# Bluetooth.net
KiCad netlist of a schematic drawn in Altium Designer
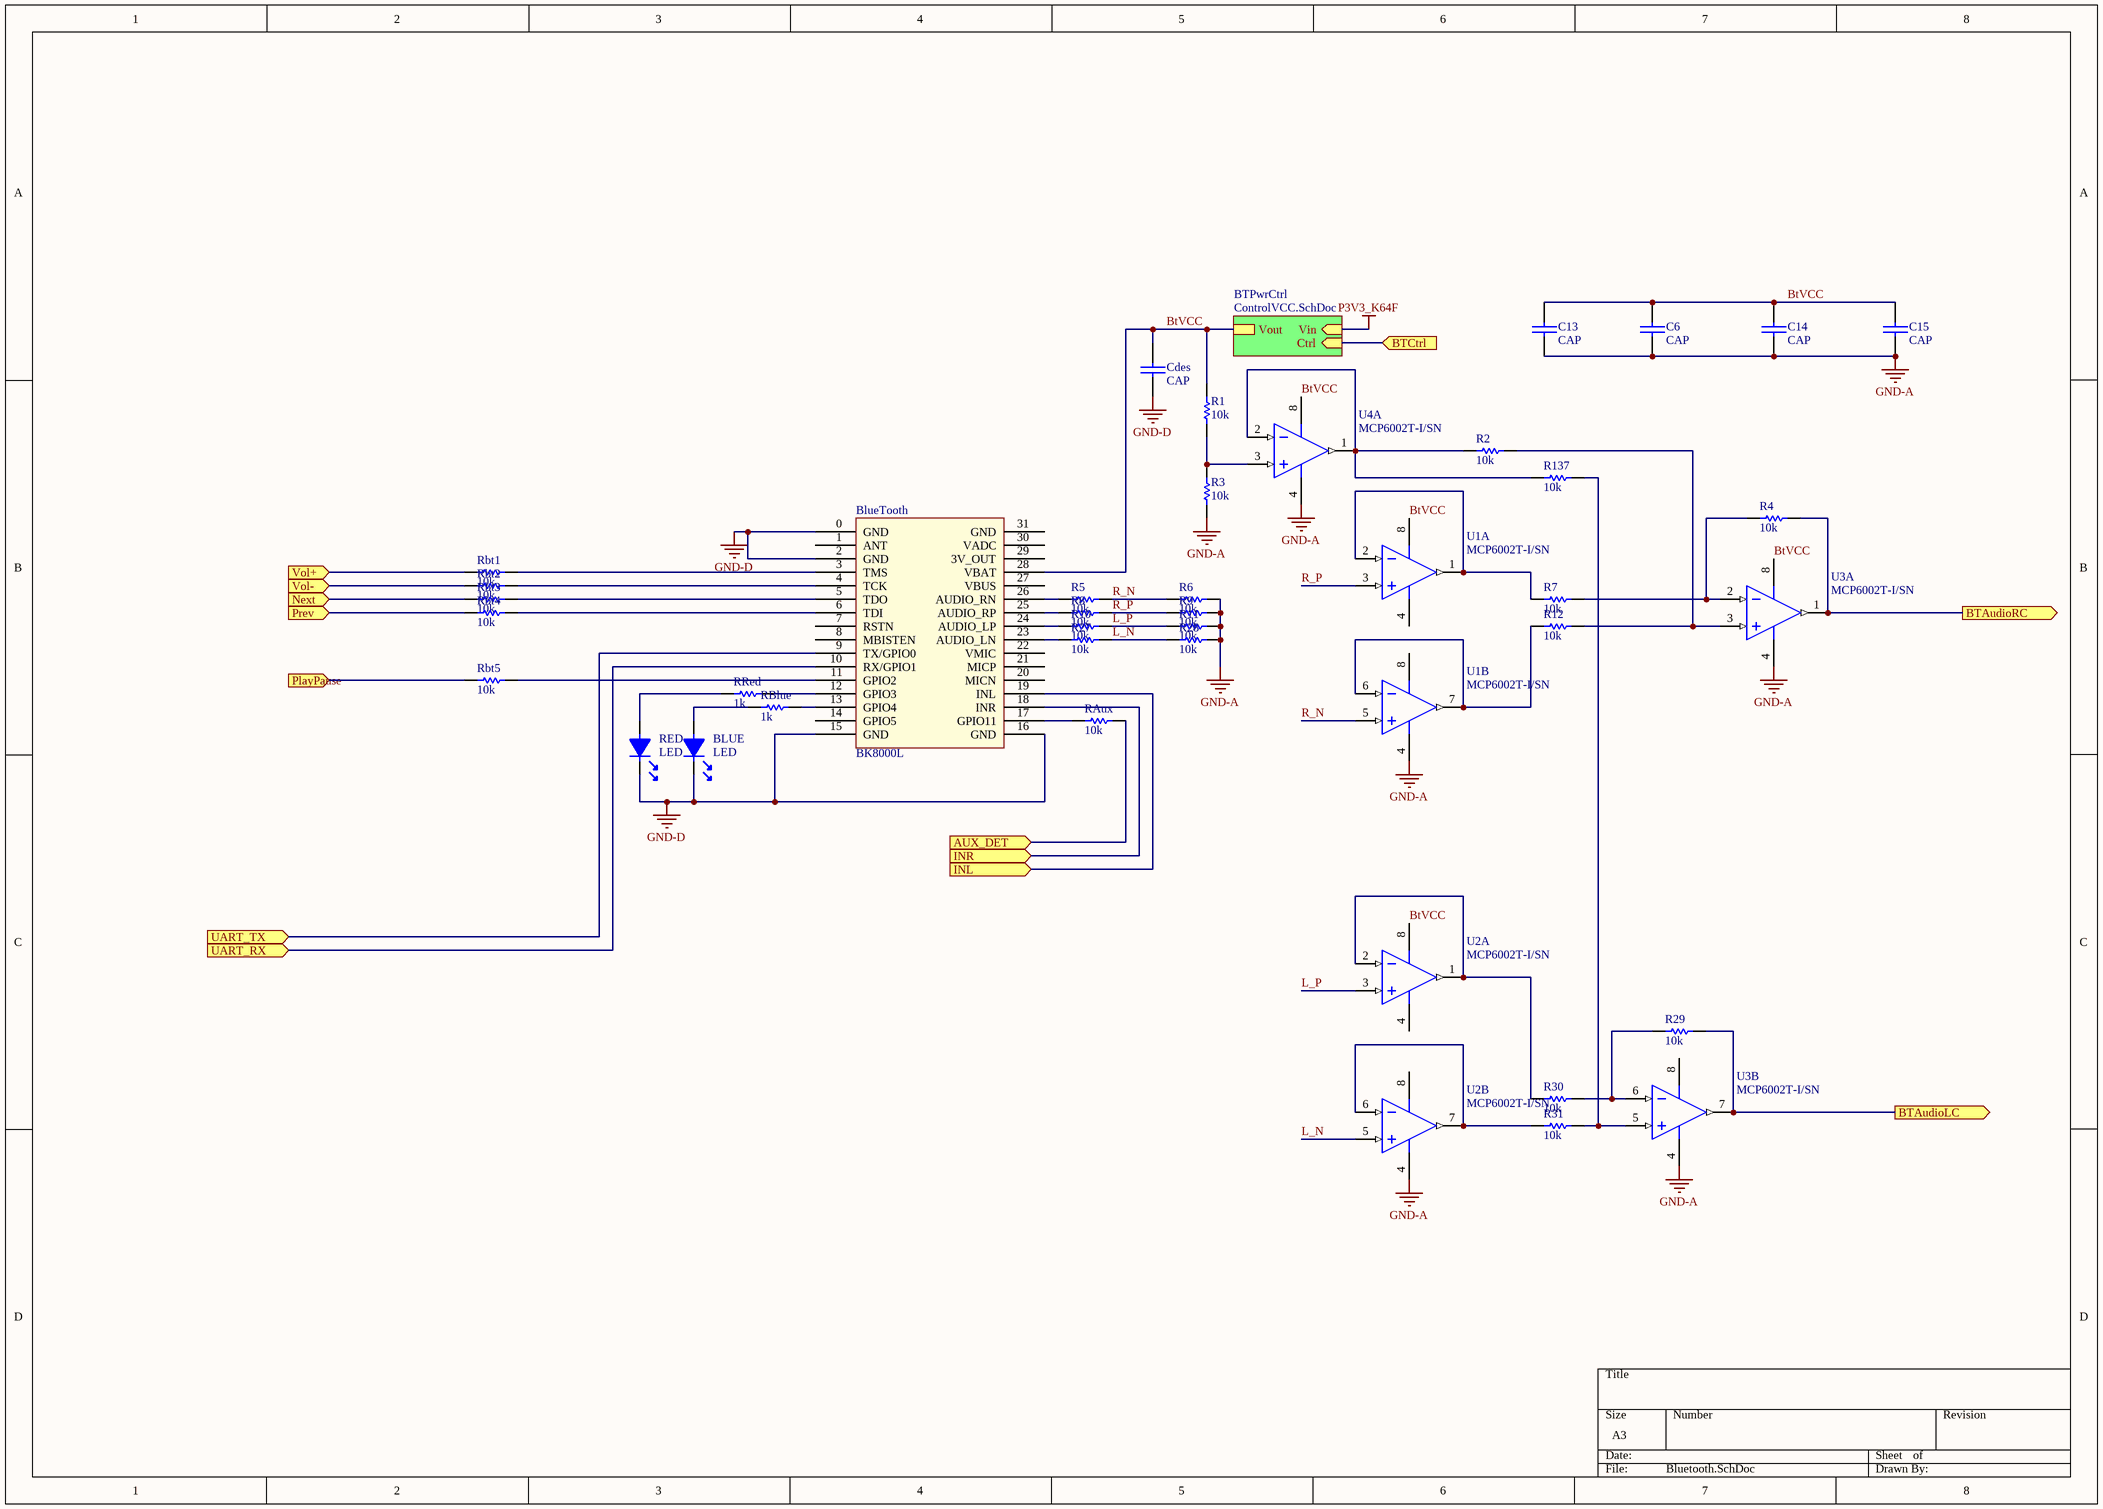
[diagram p0: Bluetooth.SchDoc]

(export (version "E")
  (design (tool "Eeschema 10.0.6"))
  (components
    (comp (ref "BLUE") (value "LED") (footprint "0805") (libsource (lib "LIBEBAL") (part "LED")))
    (comp (ref "BlueTooth")
      (value "BK8000L")
      (footprint "BK8000L")
      (libsource (lib "BK8000L") (part "BK8000L"))
    )
    (comp (ref "C6") (value "CAP") (footprint "0805") (libsource (lib "LIBEBAL") (part "CAP")))
    (comp (ref "C13") (value "CAP") (footprint "0805") (libsource (lib "LIBEBAL") (part "CAP")))
    (comp (ref "C14") (value "CAP") (footprint "0805") (libsource (lib "LIBEBAL") (part "CAP")))
    (comp (ref "C15") (value "CAP") (footprint "0805") (libsource (lib "LIBEBAL") (part "CAP")))
    (comp (ref "Cdes") (value "CAP") (footprint "0805") (libsource (lib "LIBEBAL") (part "CAP")))
    (comp (ref "R1") (value "10k") (footprint "0805") (libsource (lib "LIBEBAL") (part "RES")))
    (comp (ref "R2") (value "10k") (footprint "0805") (libsource (lib "LIBEBAL") (part "RES")))
    (comp (ref "R3") (value "10k") (footprint "0805") (libsource (lib "LIBEBAL") (part "RES")))
    (comp (ref "R4") (value "10k") (footprint "0805") (libsource (lib "LIBEBAL") (part "RES")))
    (comp (ref "R5") (value "10k") (footprint "0805") (libsource (lib "LIBEBAL") (part "RES")))
    (comp (ref "R6") (value "10k") (footprint "0805") (libsource (lib "LIBEBAL") (part "RES")))
    (comp (ref "R7") (value "10k") (footprint "0805") (libsource (lib "LIBEBAL") (part "RES")))
    (comp (ref "R8") (value "10k") (footprint "0805") (libsource (lib "LIBEBAL") (part "RES")))
    (comp (ref "R9") (value "10k") (footprint "0805") (libsource (lib "LIBEBAL") (part "RES")))
    (comp (ref "R10") (value "10k") (footprint "0805") (libsource (lib "LIBEBAL") (part "RES")))
    (comp (ref "R11") (value "10k") (footprint "0805") (libsource (lib "LIBEBAL") (part "RES")))
    (comp (ref "R12") (value "10k") (footprint "0805") (libsource (lib "LIBEBAL") (part "RES")))
    (comp (ref "R27") (value "10k") (footprint "0805") (libsource (lib "LIBEBAL") (part "RES")))
    (comp (ref "R28") (value "10k") (footprint "0805") (libsource (lib "LIBEBAL") (part "RES")))
    (comp (ref "R29") (value "10k") (footprint "0805") (libsource (lib "LIBEBAL") (part "RES")))
    (comp (ref "R30") (value "10k") (footprint "0805") (libsource (lib "LIBEBAL") (part "RES")))
    (comp (ref "R31") (value "10k") (footprint "0805") (libsource (lib "LIBEBAL") (part "RES")))
    (comp (ref "R137") (value "10k") (footprint "0805") (libsource (lib "LIBEBAL") (part "RES")))
    (comp (ref "RAux") (value "10k") (footprint "0805") (libsource (lib "LIBEBAL") (part "RES")))
    (comp (ref "RBlue") (value "1k") (footprint "0805") (libsource (lib "LIBEBAL") (part "RES")))
    (comp (ref "Rbt1") (value "10k") (footprint "0805") (libsource (lib "LIBEBAL") (part "RES")))
    (comp (ref "Rbt2") (value "10k") (footprint "0805") (libsource (lib "LIBEBAL") (part "RES")))
    (comp (ref "Rbt3") (value "10k") (footprint "0805") (libsource (lib "LIBEBAL") (part "RES")))
    (comp (ref "Rbt4") (value "10k") (footprint "0805") (libsource (lib "LIBEBAL") (part "RES")))
    (comp (ref "Rbt5") (value "10k") (footprint "0805") (libsource (lib "LIBEBAL") (part "RES")))
    (comp (ref "RED") (value "LED") (footprint "0805") (libsource (lib "LIBEBAL") (part "LED")))
    (comp (ref "RRed") (value "1k") (footprint "0805") (libsource (lib "LIBEBAL") (part "RES")))
    (comp (ref "U1")
      (value "MCP6002T-I/SN")
      (footprint "SOIC-SN8_N")
      (description "1 MHz, Low-Power Operational Amplifier, 8-Pin SOIC, Industrial Temperature, Tape and Reel")
      (fields (field (name "PUBLISHER") "Altium Limited"))
      (libsource (lib "Microchip Linear Devices") (part "MCP6002T-I/SN"))
    )
    (comp (ref "U2")
      (value "MCP6002T-I/SN")
      (footprint "SOIC-SN8_N")
      (description "1 MHz, Low-Power Operational Amplifier, 8-Pin SOIC, Industrial Temperature, Tape and Reel")
      (fields (field (name "PUBLISHER") "Altium Limited"))
      (libsource (lib "Microchip Linear Devices") (part "MCP6002T-I/SN"))
    )
    (comp (ref "U3")
      (value "MCP6002T-I/SN")
      (footprint "SOIC-SN8_N")
      (description "1 MHz, Low-Power Operational Amplifier, 8-Pin SOIC, Industrial Temperature, Tape and Reel")
      (fields (field (name "PUBLISHER") "Altium Limited"))
      (libsource (lib "Microchip Linear Devices") (part "MCP6002T-I/SN"))
    )
    (comp (ref "U4")
      (value "MCP6002T-I/SN")
      (footprint "SOIC-SN8_N")
      (description "1 MHz, Low-Power Operational Amplifier, 8-Pin SOIC, Industrial Temperature, Tape and Reel")
      (fields (field (name "PUBLISHER") "Altium Limited"))
      (libsource (lib "Microchip Linear Devices") (part "MCP6002T-I/SN"))
    )
  )
  (nets
    (net (code "1") (name "/AUX_DET") (class "Default")
      (node (ref "RAux") (pin "2") (pinfunction "2_2") (pintype "passive"))
    )
    (net (code "2") (name "/BTAudioLC") (class "Default")
      (node (ref "R29") (pin "2") (pinfunction "2_2") (pintype "passive"))
      (node (ref "U3") (pin "7") (pinfunction "VOUTB_7") (pintype "output"))
    )
    (net (code "3") (name "/BTAudioRC") (class "Default")
      (node (ref "R4") (pin "2") (pinfunction "2_2") (pintype "passive"))
      (node (ref "U3") (pin "1") (pinfunction "VOUTA_1") (pintype "output"))
    )
    (net (code "5") (name "/BtVCC") (class "Default")
      (node (ref "BlueTooth") (pin "28") (pinfunction "VBAT_28") (pintype "passive"))
      (node (ref "C13") (pin "1") (pinfunction "1_1") (pintype "passive"))
      (node (ref "C14") (pin "1") (pinfunction "1_1") (pintype "passive"))
      (node (ref "C15") (pin "1") (pinfunction "1_1") (pintype "passive"))
      (node (ref "C6") (pin "1") (pinfunction "1_1") (pintype "passive"))
      (node (ref "Cdes") (pin "1") (pinfunction "1_1") (pintype "passive"))
      (node (ref "R1") (pin "2") (pinfunction "2_2") (pintype "passive"))
      (node (ref "U1") (pin "8") (pinfunction "VDD_8") (pintype "power_in"))
      (node (ref "U2") (pin "8") (pinfunction "VDD_8") (pintype "power_in"))
      (node (ref "U3") (pin "8") (pinfunction "VDD_8") (pintype "power_in"))
      (node (ref "U4") (pin "8") (pinfunction "VDD_8") (pintype "power_in"))
    )
    (net (code "6") (name "/INL") (class "Default")
      (node (ref "BlueTooth") (pin "19") (pinfunction "INL_19") (pintype "passive"))
    )
    (net (code "7") (name "/INR") (class "Default")
      (node (ref "BlueTooth") (pin "18") (pinfunction "INR_18") (pintype "passive"))
    )
    (net (code "8") (name "/L_N") (class "Default")
      (node (ref "R27") (pin "2") (pinfunction "2_2") (pintype "passive"))
      (node (ref "R28") (pin "1") (pinfunction "1_1") (pintype "passive"))
      (node (ref "U2") (pin "5") (pinfunction "VINB+_5") (pintype "input"))
    )
    (net (code "9") (name "/L_P") (class "Default")
      (node (ref "R10") (pin "2") (pinfunction "2_2") (pintype "passive"))
      (node (ref "R11") (pin "1") (pinfunction "1_1") (pintype "passive"))
      (node (ref "U2") (pin "3") (pinfunction "VINA+_3") (pintype "input"))
    )
    (net (code "10") (name "/Next") (class "Default")
      (node (ref "Rbt3") (pin "1") (pinfunction "1_1") (pintype "passive"))
    )
    (net (code "11") (name "/PlayPause") (class "Default")
      (node (ref "Rbt5") (pin "1") (pinfunction "1_1") (pintype "passive"))
    )
    (net (code "12") (name "/Prev") (class "Default")
      (node (ref "Rbt4") (pin "1") (pinfunction "1_1") (pintype "passive"))
    )
    (net (code "13") (name "/R_N") (class "Default")
      (node (ref "R5") (pin "2") (pinfunction "2_2") (pintype "passive"))
      (node (ref "R6") (pin "1") (pinfunction "1_1") (pintype "passive"))
      (node (ref "U1") (pin "5") (pinfunction "VINB+_5") (pintype "input"))
    )
    (net (code "14") (name "/R_P") (class "Default")
      (node (ref "R8") (pin "2") (pinfunction "2_2") (pintype "passive"))
      (node (ref "R9") (pin "1") (pinfunction "1_1") (pintype "passive"))
      (node (ref "U1") (pin "3") (pinfunction "VINA+_3") (pintype "input"))
    )
    (net (code "15") (name "/UART_RX") (class "Default")
      (node (ref "BlueTooth") (pin "10") (pinfunction "RX/GPIO1_10") (pintype "passive"))
    )
    (net (code "16") (name "/UART_TX") (class "Default")
      (node (ref "BlueTooth") (pin "9") (pinfunction "TX/GPIO0_9") (pintype "passive"))
    )
    (net (code "17") (name "/Vol+") (class "Default")
      (node (ref "Rbt1") (pin "1") (pinfunction "1_1") (pintype "passive"))
    )
    (net (code "18") (name "/Vol-") (class "Default")
      (node (ref "Rbt2") (pin "1") (pinfunction "1_1") (pintype "passive"))
    )
    (net (code "19") (name "GND-A") (class "Default")
      (node (ref "C13") (pin "2") (pinfunction "2_2") (pintype "passive"))
      (node (ref "C14") (pin "2") (pinfunction "2_2") (pintype "passive"))
      (node (ref "C15") (pin "2") (pinfunction "2_2") (pintype "passive"))
      (node (ref "C6") (pin "2") (pinfunction "2_2") (pintype "passive"))
      (node (ref "R11") (pin "2") (pinfunction "2_2") (pintype "passive"))
      (node (ref "R28") (pin "2") (pinfunction "2_2") (pintype "passive"))
      (node (ref "R3") (pin "1") (pinfunction "1_1") (pintype "passive"))
      (node (ref "R6") (pin "2") (pinfunction "2_2") (pintype "passive"))
      (node (ref "R9") (pin "2") (pinfunction "2_2") (pintype "passive"))
      (node (ref "U1") (pin "4") (pinfunction "VSS_4") (pintype "power_in"))
      (node (ref "U2") (pin "4") (pinfunction "VSS_4") (pintype "power_in"))
      (node (ref "U3") (pin "4") (pinfunction "VSS_4") (pintype "power_in"))
      (node (ref "U4") (pin "4") (pinfunction "VSS_4") (pintype "power_in"))
    )
    (net (code "20") (name "GND-D") (class "Default")
      (node (ref "BLUE") (pin "2") (pinfunction "2_2") (pintype "passive"))
      (node (ref "BlueTooth") (pin "0") (pinfunction "GND_0") (pintype "passive"))
      (node (ref "BlueTooth") (pin "15") (pinfunction "GND_15") (pintype "passive"))
      (node (ref "BlueTooth") (pin "16") (pinfunction "GND_16") (pintype "passive"))
      (node (ref "BlueTooth") (pin "2") (pinfunction "GND_2") (pintype "passive"))
      (node (ref "Cdes") (pin "2") (pinfunction "2_2") (pintype "passive"))
      (node (ref "RED") (pin "2") (pinfunction "2_2") (pintype "passive"))
    )
    (net (code "21") (name "Net-(BLUE-Pad1)") (class "Default")
      (node (ref "BLUE") (pin "1") (pinfunction "1_1") (pintype "passive"))
      (node (ref "RBlue") (pin "1") (pinfunction "1_1") (pintype "passive"))
    )
    (net (code "22") (name "Net-(BlueTooth-AUDIO_LN)") (class "Default")
      (node (ref "BlueTooth") (pin "23") (pinfunction "AUDIO_LN_23") (pintype "passive"))
      (node (ref "R27") (pin "1") (pinfunction "1_1") (pintype "passive"))
    )
    (net (code "23") (name "Net-(BlueTooth-AUDIO_LP)") (class "Default")
      (node (ref "BlueTooth") (pin "24") (pinfunction "AUDIO_LP_24") (pintype "passive"))
      (node (ref "R10") (pin "1") (pinfunction "1_1") (pintype "passive"))
    )
    (net (code "24") (name "Net-(BlueTooth-AUDIO_RN)") (class "Default")
      (node (ref "BlueTooth") (pin "26") (pinfunction "AUDIO_RN_26") (pintype "passive"))
      (node (ref "R5") (pin "1") (pinfunction "1_1") (pintype "passive"))
    )
    (net (code "25") (name "Net-(BlueTooth-AUDIO_RP)") (class "Default")
      (node (ref "BlueTooth") (pin "25") (pinfunction "AUDIO_RP_25") (pintype "passive"))
      (node (ref "R8") (pin "1") (pinfunction "1_1") (pintype "passive"))
    )
    (net (code "26") (name "Net-(BlueTooth-GPIO2)") (class "Default")
      (node (ref "BlueTooth") (pin "11") (pinfunction "GPIO2_11") (pintype "passive"))
      (node (ref "Rbt5") (pin "2") (pinfunction "2_2") (pintype "passive"))
    )
    (net (code "27") (name "Net-(BlueTooth-GPIO3)") (class "Default")
      (node (ref "BlueTooth") (pin "12") (pinfunction "GPIO3_12") (pintype "passive"))
      (node (ref "RRed") (pin "2") (pinfunction "2_2") (pintype "passive"))
    )
    (net (code "28") (name "Net-(BlueTooth-GPIO4)") (class "Default")
      (node (ref "BlueTooth") (pin "13") (pinfunction "GPIO4_13") (pintype "passive"))
      (node (ref "RBlue") (pin "2") (pinfunction "2_2") (pintype "passive"))
    )
    (net (code "29") (name "Net-(BlueTooth-GPIO11)") (class "Default")
      (node (ref "BlueTooth") (pin "17") (pinfunction "GPIO11_17") (pintype "passive"))
      (node (ref "RAux") (pin "1") (pinfunction "1_1") (pintype "passive"))
    )
    (net (code "30") (name "Net-(BlueTooth-TCK)") (class "Default")
      (node (ref "BlueTooth") (pin "4") (pinfunction "TCK_4") (pintype "passive"))
      (node (ref "Rbt2") (pin "2") (pinfunction "2_2") (pintype "passive"))
    )
    (net (code "31") (name "Net-(BlueTooth-TDI)") (class "Default")
      (node (ref "BlueTooth") (pin "6") (pinfunction "TDI_6") (pintype "passive"))
      (node (ref "Rbt4") (pin "2") (pinfunction "2_2") (pintype "passive"))
    )
    (net (code "32") (name "Net-(BlueTooth-TDO)") (class "Default")
      (node (ref "BlueTooth") (pin "5") (pinfunction "TDO_5") (pintype "passive"))
      (node (ref "Rbt3") (pin "2") (pinfunction "2_2") (pintype "passive"))
    )
    (net (code "33") (name "Net-(BlueTooth-TMS)") (class "Default")
      (node (ref "BlueTooth") (pin "3") (pinfunction "TMS_3") (pintype "passive"))
      (node (ref "Rbt1") (pin "2") (pinfunction "2_2") (pintype "passive"))
    )
    (net (code "34") (name "Net-(RED-Pad1)") (class "Default")
      (node (ref "RED") (pin "1") (pinfunction "1_1") (pintype "passive"))
      (node (ref "RRed") (pin "1") (pinfunction "1_1") (pintype "passive"))
    )
    (net (code "35") (name "Net-(U1A-VINA-)") (class "Default")
      (node (ref "R7") (pin "1") (pinfunction "1_1") (pintype "passive"))
      (node (ref "U1") (pin "1") (pinfunction "VOUTA_1") (pintype "output"))
      (node (ref "U1") (pin "2") (pinfunction "VINA-_2") (pintype "input"))
    )
    (net (code "36") (name "Net-(U1B-VINB-)") (class "Default")
      (node (ref "R12") (pin "1") (pinfunction "1_1") (pintype "passive"))
      (node (ref "U1") (pin "6") (pinfunction "VINB-_6") (pintype "input"))
      (node (ref "U1") (pin "7") (pinfunction "VOUTB_7") (pintype "output"))
    )
    (net (code "37") (name "Net-(U2A-VINA-)") (class "Default")
      (node (ref "R30") (pin "1") (pinfunction "1_1") (pintype "passive"))
      (node (ref "U2") (pin "1") (pinfunction "VOUTA_1") (pintype "output"))
      (node (ref "U2") (pin "2") (pinfunction "VINA-_2") (pintype "input"))
    )
    (net (code "38") (name "Net-(U2B-VINB-)") (class "Default")
      (node (ref "R31") (pin "1") (pinfunction "1_1") (pintype "passive"))
      (node (ref "U2") (pin "6") (pinfunction "VINB-_6") (pintype "input"))
      (node (ref "U2") (pin "7") (pinfunction "VOUTB_7") (pintype "output"))
    )
    (net (code "39") (name "Net-(U3A-VINA+)") (class "Default")
      (node (ref "R12") (pin "2") (pinfunction "2_2") (pintype "passive"))
      (node (ref "R2") (pin "2") (pinfunction "2_2") (pintype "passive"))
      (node (ref "U3") (pin "3") (pinfunction "VINA+_3") (pintype "input"))
    )
    (net (code "40") (name "Net-(U3A-VINA-)") (class "Default")
      (node (ref "R4") (pin "1") (pinfunction "1_1") (pintype "passive"))
      (node (ref "R7") (pin "2") (pinfunction "2_2") (pintype "passive"))
      (node (ref "U3") (pin "2") (pinfunction "VINA-_2") (pintype "input"))
    )
    (net (code "41") (name "Net-(U3B-VINB+)") (class "Default")
      (node (ref "R137") (pin "2") (pinfunction "2_2") (pintype "passive"))
      (node (ref "R31") (pin "2") (pinfunction "2_2") (pintype "passive"))
      (node (ref "U3") (pin "5") (pinfunction "VINB+_5") (pintype "input"))
    )
    (net (code "42") (name "Net-(U3B-VINB-)") (class "Default")
      (node (ref "R29") (pin "1") (pinfunction "1_1") (pintype "passive"))
      (node (ref "R30") (pin "2") (pinfunction "2_2") (pintype "passive"))
      (node (ref "U3") (pin "6") (pinfunction "VINB-_6") (pintype "input"))
    )
    (net (code "43") (name "Net-(U4A-VINA+)") (class "Default")
      (node (ref "R1") (pin "1") (pinfunction "1_1") (pintype "passive"))
      (node (ref "R3") (pin "2") (pinfunction "2_2") (pintype "passive"))
      (node (ref "U4") (pin "3") (pinfunction "VINA+_3") (pintype "input"))
    )
    (net (code "44") (name "Net-(U4A-VINA-)") (class "Default")
      (node (ref "R137") (pin "1") (pinfunction "1_1") (pintype "passive"))
      (node (ref "R2") (pin "1") (pinfunction "1_1") (pintype "passive"))
      (node (ref "U4") (pin "1") (pinfunction "VOUTA_1") (pintype "output"))
      (node (ref "U4") (pin "2") (pinfunction "VINA-_2") (pintype "input"))
    )
    (net (code "46") (name "unconnected-(BlueTooth-3V_OUT-Pad29)") (class "Default")
      (node (ref "BlueTooth") (pin "29") (pinfunction "3V_OUT_29") (pintype "passive"))
    )
    (net (code "47") (name "unconnected-(BlueTooth-ANT-Pad1)") (class "Default")
      (node (ref "BlueTooth") (pin "1") (pinfunction "ANT_1") (pintype "passive"))
    )
    (net (code "48") (name "unconnected-(BlueTooth-GND-Pad31)") (class "Default")
      (node (ref "BlueTooth") (pin "31") (pinfunction "GND_31") (pintype "passive"))
    )
    (net (code "49") (name "unconnected-(BlueTooth-GPIO5-Pad14)") (class "Default")
      (node (ref "BlueTooth") (pin "14") (pinfunction "GPIO5_14") (pintype "passive"))
    )
    (net (code "50") (name "unconnected-(BlueTooth-MBISTEN-Pad8)") (class "Default")
      (node (ref "BlueTooth") (pin "8") (pinfunction "MBISTEN_8") (pintype "passive"))
    )
    (net (code "51") (name "unconnected-(BlueTooth-MICN-Pad20)") (class "Default")
      (node (ref "BlueTooth") (pin "20") (pinfunction "MICN_20") (pintype "passive"))
    )
    (net (code "52") (name "unconnected-(BlueTooth-MICP-Pad21)") (class "Default")
      (node (ref "BlueTooth") (pin "21") (pinfunction "MICP_21") (pintype "passive"))
    )
    (net (code "53") (name "unconnected-(BlueTooth-RSTN-Pad7)") (class "Default")
      (node (ref "BlueTooth") (pin "7") (pinfunction "RSTN_7") (pintype "passive"))
    )
    (net (code "54") (name "unconnected-(BlueTooth-VADC-Pad30)") (class "Default")
      (node (ref "BlueTooth") (pin "30") (pinfunction "VADC_30") (pintype "passive"))
    )
    (net (code "55") (name "unconnected-(BlueTooth-VBUS-Pad27)") (class "Default")
      (node (ref "BlueTooth") (pin "27") (pinfunction "VBUS_27") (pintype "passive"))
    )
    (net (code "56") (name "unconnected-(BlueTooth-VMIC-Pad22)") (class "Default")
      (node (ref "BlueTooth") (pin "22") (pinfunction "VMIC_22") (pintype "passive"))
    )
    (net (code "57") (name "unconnected-(U1A-VSS-Pad4)") (class "Default")
      (node (ref "U1") (pin "4") (pinfunction "VSS_4") (pintype "power_in"))
    )
    (net (code "58") (name "unconnected-(U1B-VDD-Pad8)") (class "Default")
      (node (ref "U1") (pin "8") (pinfunction "VDD_8") (pintype "power_in"))
    )
    (net (code "59") (name "unconnected-(U2A-VSS-Pad4)") (class "Default")
      (node (ref "U2") (pin "4") (pinfunction "VSS_4") (pintype "power_in"))
    )
    (net (code "60") (name "unconnected-(U2B-VDD-Pad8)") (class "Default")
      (node (ref "U2") (pin "8") (pinfunction "VDD_8") (pintype "power_in"))
    )
    (net (code "61") (name "unconnected-(U3B-VDD-Pad8)") (class "Default")
      (node (ref "U3") (pin "8") (pinfunction "VDD_8") (pintype "power_in"))
    )
  )
)
